# Domino_Single_Ethernet_PoE_No_Teardrop.net
KiCad netlist of a schematic drawn in EAGLE
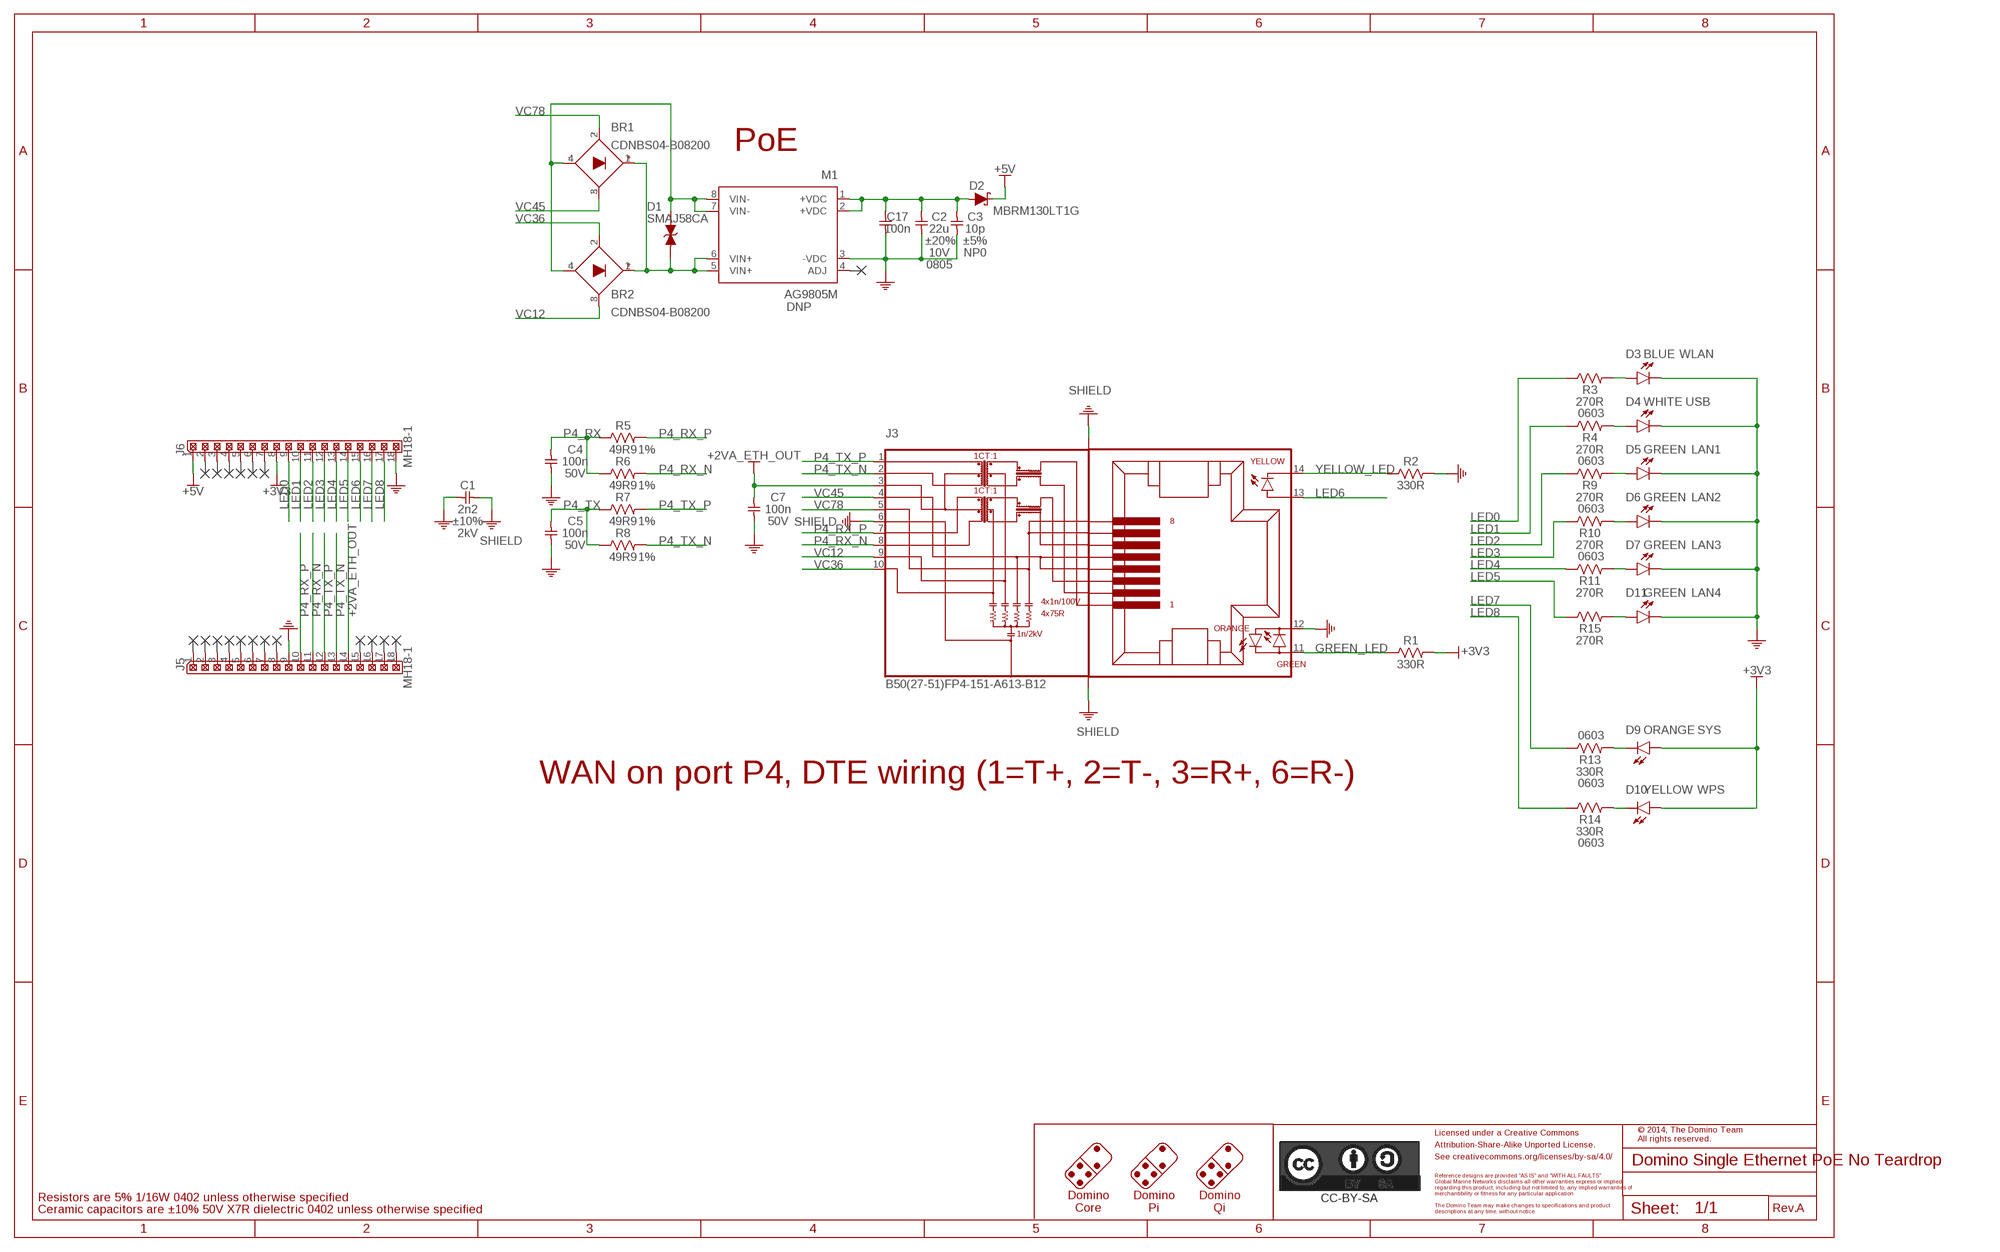
[diagram p0: schematic, sheet 1]

(export (version "E")
  (design (tool "Eeschema 10.0.6"))
  (components
    (comp (ref "BR1")
      (value "CDNBS04-B08200")
      (footprint "eagle-import:NBS04")
      (libsource (lib "eagle-import") (part "CDNBS04-B08200"))
    )
    (comp (ref "BR2")
      (value "CDNBS04-B08200")
      (footprint "eagle-import:NBS04")
      (libsource (lib "eagle-import") (part "CDNBS04-B08200"))
    )
    (comp (ref "C1")
      (value "2n2")
      (footprint "eagle-import:C1206")
      (fields
        (field (name "PARTNO") "C1210_2n2_X7R_10%_CER_2kV")
        (field (name "TOL") "±10%")
        (field (name "VOLT") "2kV")
      )
      (libsource (lib "eagle-import") (part "CAP_1206"))
    )
    (comp (ref "C2")
      (value "22u")
      (footprint "eagle-import:C0805")
      (fields
        (field (name "SIZE") "0805")
        (field (name "PARTNO") "C1206_22u_X7R_20%_CER_10V")
        (field (name "TOL") "±20%")
        (field (name "VOLT") "10V")
      )
      (libsource (lib "eagle-import") (part "CAP_0805"))
    )
    (comp (ref "C3")
      (value "10p")
      (footprint "eagle-import:C0402")
      (fields
        (field (name "PARTNO") "C0402_10p_NP0_5%_CER_50V")
        (field (name "TC") "NP0")
        (field (name "TOL") "±5%")
      )
      (libsource (lib "eagle-import") (part "CAP_0402"))
    )
    (comp (ref "C4")
      (value "100n")
      (footprint "eagle-import:C0402")
      (fields (field (name "PARTNO") "C0402_100n_X7R_10%_CER_50V") (field (name "VOLT") "50V"))
      (libsource (lib "eagle-import") (part "CAP_0402"))
    )
    (comp (ref "C5")
      (value "100n")
      (footprint "eagle-import:C0402")
      (fields (field (name "PARTNO") "C0402_100n_X7R_10%_CER_50V") (field (name "VOLT") "50V"))
      (libsource (lib "eagle-import") (part "CAP_0402"))
    )
    (comp (ref "C7")
      (value "100n")
      (footprint "eagle-import:C0402")
      (fields (field (name "PARTNO") "C0402_100n_X7R_10%_CER_50V") (field (name "VOLT") "50V"))
      (libsource (lib "eagle-import") (part "CAP_0402"))
    )
    (comp (ref "C17")
      (value "100n")
      (footprint "eagle-import:C0402")
      (fields (field (name "PARTNO") "C0402_100n_X7R_10%_CER_50V"))
      (libsource (lib "eagle-import") (part "CAP_0402"))
    )
    (comp (ref "CC-BY-SA1")
      (value "CC-BY-SA_LOGO")
      (footprint "eagle-import:CC-BY-SA_LOGO")
      (libsource (lib "eagle-import") (part "CC-BY-SA_LOGO"))
    )
    (comp (ref "D1")
      (value "SMAJ58CA")
      (footprint "eagle-import:SMA")
      (libsource (lib "eagle-import") (part "SMAJ58CA"))
    )
    (comp (ref "D2")
      (value "MBRM130LT1G")
      (footprint "eagle-import:DO-216AA")
      (libsource (lib "eagle-import") (part "MBRM130LT1G"))
    )
    (comp (ref "D3")
      (value "BLUE")
      (footprint "eagle-import:LED0603")
      (fields (field (name "PARTNO") "LED0603-BLUE"))
      (libsource (lib "eagle-import") (part "LED_0603"))
    )
    (comp (ref "D4")
      (value "WHITE")
      (footprint "eagle-import:LED0603")
      (fields (field (name "PARTNO") "LED0603-WHITE"))
      (libsource (lib "eagle-import") (part "LED_0603"))
    )
    (comp (ref "D5")
      (value "GREEN")
      (footprint "eagle-import:LED0603")
      (fields (field (name "PARTNO") "LED0603-GREEN"))
      (libsource (lib "eagle-import") (part "LED_0603"))
    )
    (comp (ref "D6")
      (value "GREEN")
      (footprint "eagle-import:LED0603")
      (fields (field (name "PARTNO") "LED0603-GREEN"))
      (libsource (lib "eagle-import") (part "LED_0603"))
    )
    (comp (ref "D7")
      (value "GREEN")
      (footprint "eagle-import:LED0603")
      (fields (field (name "PARTNO") "LED0603-GREEN"))
      (libsource (lib "eagle-import") (part "LED_0603"))
    )
    (comp (ref "D9")
      (value "ORANGE")
      (footprint "eagle-import:LED0603")
      (fields (field (name "PARTNO") "LED0603-ORANGE"))
      (libsource (lib "eagle-import") (part "LED_0603"))
    )
    (comp (ref "D10")
      (value "YELLOW")
      (footprint "eagle-import:LED0603")
      (fields (field (name "PARTNO") "LED0603-YELLOW"))
      (libsource (lib "eagle-import") (part "LED_0603"))
    )
    (comp (ref "D11")
      (value "GREEN")
      (footprint "eagle-import:LED0603")
      (fields (field (name "PARTNO") "LED0603-GREEN"))
      (libsource (lib "eagle-import") (part "LED_0603"))
    )
    (comp (ref "J3")
      (value "B50(27-51)FP4-151-A613-B12")
      (footprint "eagle-import:B50(27-51)FP4-151-A613-B12")
      (libsource (lib "eagle-import") (part "B50(27-51)FP4-151-A613-B12"))
    )
    (comp (ref "J5")
      (value "MH18-1")
      (footprint "eagle-import:MH18-1-0.1")
      (libsource (lib "eagle-import") (part "MH18-1"))
    )
    (comp (ref "J6")
      (value "MH18-1")
      (footprint "eagle-import:MH18-1-0.1")
      (libsource (lib "eagle-import") (part "MH18-1"))
    )
    (comp (ref "M1")
      (value "AG9805M")
      (footprint "eagle-import:AG9800M")
      (fields (field (name "PARTNO") "Ag9800M"))
      (libsource (lib "eagle-import") (part "AG98M05"))
    )
    (comp (ref "R1")
      (value "330R")
      (footprint "eagle-import:R0402")
      (fields (field (name "PARTNO") "R0402_330R_5%_62.5mW"))
      (libsource (lib "eagle-import") (part "RES_0402"))
    )
    (comp (ref "R2")
      (value "330R")
      (footprint "eagle-import:R0402")
      (fields (field (name "PARTNO") "R0402_330R_5%_62.5mW"))
      (libsource (lib "eagle-import") (part "RES_0402"))
    )
    (comp (ref "R3")
      (value "270R")
      (footprint "eagle-import:R0603")
      (fields (field (name "SIZE") "0603") (field (name "PARTNO") "R0603_270R_5%_125mW"))
      (libsource (lib "eagle-import") (part "RES_0603"))
    )
    (comp (ref "R4")
      (value "270R")
      (footprint "eagle-import:R0603")
      (fields (field (name "SIZE") "0603") (field (name "PARTNO") "R0603_270R_5%_125mW"))
      (libsource (lib "eagle-import") (part "RES_0603"))
    )
    (comp (ref "R5")
      (value "49R9")
      (footprint "eagle-import:R0402")
      (fields (field (name "PARTNO") "R0402_49R9_1%_62.5mW") (field (name "TOL") "1%"))
      (libsource (lib "eagle-import") (part "RES_0402"))
    )
    (comp (ref "R6")
      (value "49R9")
      (footprint "eagle-import:R0402")
      (fields (field (name "PARTNO") "R0402_49R9_1%_62.5mW") (field (name "TOL") "1%"))
      (libsource (lib "eagle-import") (part "RES_0402"))
    )
    (comp (ref "R7")
      (value "49R9")
      (footprint "eagle-import:R0402")
      (fields (field (name "PARTNO") "R0402_49R9_1%_62.5mW") (field (name "TOL") "1%"))
      (libsource (lib "eagle-import") (part "RES_0402"))
    )
    (comp (ref "R8")
      (value "49R9")
      (footprint "eagle-import:R0402")
      (fields (field (name "PARTNO") "R0402_49R9_1%_62.5mW") (field (name "TOL") "1%"))
      (libsource (lib "eagle-import") (part "RES_0402"))
    )
    (comp (ref "R9")
      (value "270R")
      (footprint "eagle-import:R0603")
      (fields (field (name "SIZE") "0603") (field (name "PARTNO") "R0603_270R_5%_125mW"))
      (libsource (lib "eagle-import") (part "RES_0603"))
    )
    (comp (ref "R10")
      (value "270R")
      (footprint "eagle-import:R0603")
      (fields (field (name "SIZE") "0603") (field (name "PARTNO") "R0603_270R_5%_125mW"))
      (libsource (lib "eagle-import") (part "RES_0603"))
    )
    (comp (ref "R11")
      (value "270R")
      (footprint "eagle-import:R0603")
      (fields (field (name "PARTNO") "R0603_270R_5%_125mW"))
      (libsource (lib "eagle-import") (part "RES_0603"))
    )
    (comp (ref "R13")
      (value "330R")
      (footprint "eagle-import:R0603")
      (fields (field (name "SIZE") "0603") (field (name "PARTNO") "R0603_330R_5%_125mW"))
      (libsource (lib "eagle-import") (part "RES_0603"))
    )
    (comp (ref "R14")
      (value "330R")
      (footprint "eagle-import:R0603")
      (fields (field (name "SIZE") "0603") (field (name "PARTNO") "R0603_330R_5%_125mW"))
      (libsource (lib "eagle-import") (part "RES_0603"))
    )
    (comp (ref "R15")
      (value "270R")
      (footprint "eagle-import:R0603")
      (fields (field (name "SIZE") "0603") (field (name "PARTNO") "R0603_270R_5%_125mW"))
      (libsource (lib "eagle-import") (part "RES_0603"))
    )
  )
  (nets
    (net (code "1") (name "+2VA_ETH_OUT") (class "Default")
      (node (ref "C7") (pin "2") (pinfunction "2_2") (pintype "passive"))
      (node (ref "J3") (pin "3") (pinfunction "3_3") (pintype "passive"))
      (node (ref "J5") (pin "14") (pinfunction "14_14") (pintype "passive"))
    )
    (net (code "2") (name "+3V3") (class "Default")
      (node (ref "D10") (pin "2") (pinfunction "A_2") (pintype "passive"))
      (node (ref "D9") (pin "2") (pinfunction "A_2") (pintype "passive"))
      (node (ref "J6") (pin "8") (pinfunction "8_8") (pintype "passive"))
      (node (ref "R1") (pin "2") (pinfunction "2_2") (pintype "passive"))
    )
    (net (code "3") (name "+5V") (class "Default")
      (node (ref "D2") (pin "1") (pinfunction "C_1") (pintype "passive"))
      (node (ref "J6") (pin "1") (pinfunction "1_1") (pintype "passive"))
    )
    (net (code "4") (name "/GREEN_LED") (class "Default")
      (node (ref "J3") (pin "11") (pinfunction "11_11") (pintype "passive"))
      (node (ref "R1") (pin "1") (pinfunction "1_1") (pintype "passive"))
    )
    (net (code "5") (name "/LED0") (class "Default")
      (node (ref "J6") (pin "9") (pinfunction "9_9") (pintype "passive"))
      (node (ref "R3") (pin "1") (pinfunction "1_1") (pintype "passive"))
    )
    (net (code "6") (name "/LED1") (class "Default")
      (node (ref "J6") (pin "10") (pinfunction "10_10") (pintype "passive"))
      (node (ref "R4") (pin "1") (pinfunction "1_1") (pintype "passive"))
    )
    (net (code "7") (name "/LED2") (class "Default")
      (node (ref "J6") (pin "11") (pinfunction "11_11") (pintype "passive"))
      (node (ref "R9") (pin "1") (pinfunction "1_1") (pintype "passive"))
    )
    (net (code "8") (name "/LED3") (class "Default")
      (node (ref "J6") (pin "12") (pinfunction "12_12") (pintype "passive"))
      (node (ref "R10") (pin "1") (pinfunction "1_1") (pintype "passive"))
    )
    (net (code "9") (name "/LED4") (class "Default")
      (node (ref "J6") (pin "13") (pinfunction "13_13") (pintype "passive"))
      (node (ref "R11") (pin "1") (pinfunction "1_1") (pintype "passive"))
    )
    (net (code "10") (name "/LED5") (class "Default")
      (node (ref "J6") (pin "14") (pinfunction "14_14") (pintype "passive"))
      (node (ref "R15") (pin "1") (pinfunction "1_1") (pintype "passive"))
    )
    (net (code "11") (name "/LED6") (class "Default")
      (node (ref "J3") (pin "13") (pinfunction "13_13") (pintype "passive"))
      (node (ref "J6") (pin "15") (pinfunction "15_15") (pintype "passive"))
    )
    (net (code "12") (name "/LED7") (class "Default")
      (node (ref "J6") (pin "16") (pinfunction "16_16") (pintype "passive"))
      (node (ref "R13") (pin "1") (pinfunction "1_1") (pintype "passive"))
    )
    (net (code "13") (name "/LED8") (class "Default")
      (node (ref "J6") (pin "17") (pinfunction "17_17") (pintype "passive"))
      (node (ref "R14") (pin "1") (pinfunction "1_1") (pintype "passive"))
    )
    (net (code "14") (name "/P4_RX") (class "Default")
      (node (ref "C4") (pin "2") (pinfunction "2_2") (pintype "passive"))
      (node (ref "R5") (pin "1") (pinfunction "1_1") (pintype "passive"))
      (node (ref "R6") (pin "1") (pinfunction "1_1") (pintype "passive"))
    )
    (net (code "15") (name "/P4_RX_N") (class "Default")
      (node (ref "J3") (pin "8") (pinfunction "8_8") (pintype "passive"))
      (node (ref "J5") (pin "11") (pinfunction "11_11") (pintype "passive"))
      (node (ref "R6") (pin "2") (pinfunction "2_2") (pintype "passive"))
    )
    (net (code "16") (name "/P4_RX_P") (class "Default")
      (node (ref "J3") (pin "7") (pinfunction "7_7") (pintype "passive"))
      (node (ref "J5") (pin "10") (pinfunction "10_10") (pintype "passive"))
      (node (ref "R5") (pin "2") (pinfunction "2_2") (pintype "passive"))
    )
    (net (code "17") (name "/P4_TX") (class "Default")
      (node (ref "C5") (pin "2") (pinfunction "2_2") (pintype "passive"))
      (node (ref "R7") (pin "1") (pinfunction "1_1") (pintype "passive"))
      (node (ref "R8") (pin "1") (pinfunction "1_1") (pintype "passive"))
    )
    (net (code "18") (name "/P4_TX_N") (class "Default")
      (node (ref "J3") (pin "2") (pinfunction "2_2") (pintype "passive"))
      (node (ref "J5") (pin "13") (pinfunction "13_13") (pintype "passive"))
      (node (ref "R8") (pin "2") (pinfunction "2_2") (pintype "passive"))
    )
    (net (code "19") (name "/P4_TX_P") (class "Default")
      (node (ref "J3") (pin "1") (pinfunction "1_1") (pintype "passive"))
      (node (ref "J5") (pin "12") (pinfunction "12_12") (pintype "passive"))
      (node (ref "R7") (pin "2") (pinfunction "2_2") (pintype "passive"))
    )
    (net (code "20") (name "/VC12") (class "Default")
      (node (ref "BR2") (pin "3") (pinfunction "AC2_3") (pintype "power_in"))
      (node (ref "J3") (pin "9") (pinfunction "9_9") (pintype "passive"))
    )
    (net (code "21") (name "/VC36") (class "Default")
      (node (ref "BR2") (pin "2") (pinfunction "AC1_2") (pintype "power_in"))
      (node (ref "J3") (pin "10") (pinfunction "10_10") (pintype "passive"))
    )
    (net (code "22") (name "/VC45") (class "Default")
      (node (ref "BR1") (pin "3") (pinfunction "AC2_3") (pintype "power_in"))
      (node (ref "J3") (pin "4") (pinfunction "4_4") (pintype "passive"))
    )
    (net (code "23") (name "/VC78") (class "Default")
      (node (ref "BR1") (pin "2") (pinfunction "AC1_2") (pintype "power_in"))
      (node (ref "J3") (pin "5") (pinfunction "5_5") (pintype "passive"))
    )
    (net (code "24") (name "/YELLOW_LED") (class "Default")
      (node (ref "J3") (pin "14") (pinfunction "14_14") (pintype "passive"))
      (node (ref "R2") (pin "1") (pinfunction "1_1") (pintype "passive"))
    )
    (net (code "25") (name "GND") (class "Default")
      (node (ref "C1") (pin "1") (pinfunction "1_1") (pintype "passive"))
      (node (ref "C17") (pin "2") (pinfunction "2_2") (pintype "passive"))
      (node (ref "C2") (pin "2") (pinfunction "2_2") (pintype "passive"))
      (node (ref "C3") (pin "2") (pinfunction "2_2") (pintype "passive"))
      (node (ref "C4") (pin "1") (pinfunction "1_1") (pintype "passive"))
      (node (ref "C5") (pin "1") (pinfunction "1_1") (pintype "passive"))
      (node (ref "C7") (pin "1") (pinfunction "1_1") (pintype "passive"))
      (node (ref "D11") (pin "1") (pinfunction "C_1") (pintype "passive"))
      (node (ref "D3") (pin "1") (pinfunction "C_1") (pintype "passive"))
      (node (ref "D4") (pin "1") (pinfunction "C_1") (pintype "passive"))
      (node (ref "D5") (pin "1") (pinfunction "C_1") (pintype "passive"))
      (node (ref "D6") (pin "1") (pinfunction "C_1") (pintype "passive"))
      (node (ref "D7") (pin "1") (pinfunction "C_1") (pintype "passive"))
      (node (ref "J3") (pin "12") (pinfunction "12_12") (pintype "passive"))
      (node (ref "J5") (pin "9") (pinfunction "9_9") (pintype "passive"))
      (node (ref "J6") (pin "18") (pinfunction "18_18") (pintype "passive"))
      (node (ref "M1") (pin "3") (pinfunction "-VDC_3") (pintype "power_in"))
      (node (ref "R2") (pin "2") (pinfunction "2_2") (pintype "passive"))
    )
    (net (code "26") (name "Net-(BR1-+)") (class "Default")
      (node (ref "BR1") (pin "1") (pinfunction "+_1") (pintype "power_in"))
      (node (ref "BR2") (pin "1") (pinfunction "+_1") (pintype "power_in"))
      (node (ref "D1") (pin "C") (pinfunction "2_C") (pintype "passive"))
      (node (ref "M1") (pin "5") (pinfunction "VIN+_5") (pintype "power_in"))
      (node (ref "M1") (pin "6") (pinfunction "VIN+_6") (pintype "power_in"))
    )
    (net (code "27") (name "Net-(BR1--)") (class "Default")
      (node (ref "BR1") (pin "4") (pinfunction "-_4") (pintype "power_in"))
      (node (ref "BR2") (pin "4") (pinfunction "-_4") (pintype "power_in"))
      (node (ref "D1") (pin "A") (pinfunction "1_A") (pintype "passive"))
      (node (ref "M1") (pin "7") (pinfunction "VIN-_7") (pintype "power_in"))
      (node (ref "M1") (pin "8") (pinfunction "VIN-_8") (pintype "power_in"))
    )
    (net (code "28") (name "Net-(D2-A)") (class "Default")
      (node (ref "C17") (pin "1") (pinfunction "1_1") (pintype "passive"))
      (node (ref "C2") (pin "1") (pinfunction "1_1") (pintype "passive"))
      (node (ref "C3") (pin "1") (pinfunction "1_1") (pintype "passive"))
      (node (ref "D2") (pin "2") (pinfunction "A_2") (pintype "passive"))
      (node (ref "M1") (pin "1") (pinfunction "+VDC_1") (pintype "power_in"))
      (node (ref "M1") (pin "2") (pinfunction "+VDC_2") (pintype "power_in"))
    )
    (net (code "29") (name "Net-(D3-A)") (class "Default")
      (node (ref "D3") (pin "2") (pinfunction "A_2") (pintype "passive"))
      (node (ref "R3") (pin "2") (pinfunction "2_2") (pintype "passive"))
    )
    (net (code "30") (name "Net-(D4-A)") (class "Default")
      (node (ref "D4") (pin "2") (pinfunction "A_2") (pintype "passive"))
      (node (ref "R4") (pin "2") (pinfunction "2_2") (pintype "passive"))
    )
    (net (code "31") (name "Net-(D5-A)") (class "Default")
      (node (ref "D5") (pin "2") (pinfunction "A_2") (pintype "passive"))
      (node (ref "R9") (pin "2") (pinfunction "2_2") (pintype "passive"))
    )
    (net (code "32") (name "Net-(D6-A)") (class "Default")
      (node (ref "D6") (pin "2") (pinfunction "A_2") (pintype "passive"))
      (node (ref "R10") (pin "2") (pinfunction "2_2") (pintype "passive"))
    )
    (net (code "33") (name "Net-(D7-A)") (class "Default")
      (node (ref "D7") (pin "2") (pinfunction "A_2") (pintype "passive"))
      (node (ref "R11") (pin "2") (pinfunction "2_2") (pintype "passive"))
    )
    (net (code "34") (name "Net-(D9-C)") (class "Default")
      (node (ref "D9") (pin "1") (pinfunction "C_1") (pintype "passive"))
      (node (ref "R13") (pin "2") (pinfunction "2_2") (pintype "passive"))
    )
    (net (code "35") (name "Net-(D10-C)") (class "Default")
      (node (ref "D10") (pin "1") (pinfunction "C_1") (pintype "passive"))
      (node (ref "R14") (pin "2") (pinfunction "2_2") (pintype "passive"))
    )
    (net (code "36") (name "Net-(D11-A)") (class "Default")
      (node (ref "D11") (pin "2") (pinfunction "A_2") (pintype "passive"))
      (node (ref "R15") (pin "2") (pinfunction "2_2") (pintype "passive"))
    )
    (net (code "37") (name "SHIELD") (class "Default")
      (node (ref "C1") (pin "2") (pinfunction "2_2") (pintype "passive"))
      (node (ref "J3") (pin "6") (pinfunction "6_6") (pintype "power_in"))
      (node (ref "J3") (pin "SH$1") (pinfunction "SHIELD_SH$1") (pintype "power_in"))
      (node (ref "J3") (pin "SH$2") (pinfunction "SHIELD_SH$2") (pintype "power_in"))
    )
    (net (code "38") (name "unconnected-(J5-Pad1)") (class "Default")
      (node (ref "J5") (pin "1") (pinfunction "1_1") (pintype "passive"))
    )
    (net (code "39") (name "unconnected-(J5-Pad2)") (class "Default")
      (node (ref "J5") (pin "2") (pinfunction "2_2") (pintype "passive"))
    )
    (net (code "40") (name "unconnected-(J5-Pad3)") (class "Default")
      (node (ref "J5") (pin "3") (pinfunction "3_3") (pintype "passive"))
    )
    (net (code "41") (name "unconnected-(J5-Pad4)") (class "Default")
      (node (ref "J5") (pin "4") (pinfunction "4_4") (pintype "passive"))
    )
    (net (code "42") (name "unconnected-(J5-Pad5)") (class "Default")
      (node (ref "J5") (pin "5") (pinfunction "5_5") (pintype "passive"))
    )
    (net (code "43") (name "unconnected-(J5-Pad6)") (class "Default")
      (node (ref "J5") (pin "6") (pinfunction "6_6") (pintype "passive"))
    )
    (net (code "44") (name "unconnected-(J5-Pad7)") (class "Default")
      (node (ref "J5") (pin "7") (pinfunction "7_7") (pintype "passive"))
    )
    (net (code "45") (name "unconnected-(J5-Pad8)") (class "Default")
      (node (ref "J5") (pin "8") (pinfunction "8_8") (pintype "passive"))
    )
    (net (code "46") (name "unconnected-(J5-Pad15)") (class "Default")
      (node (ref "J5") (pin "15") (pinfunction "15_15") (pintype "passive"))
    )
    (net (code "47") (name "unconnected-(J5-Pad16)") (class "Default")
      (node (ref "J5") (pin "16") (pinfunction "16_16") (pintype "passive"))
    )
    (net (code "48") (name "unconnected-(J5-Pad17)") (class "Default")
      (node (ref "J5") (pin "17") (pinfunction "17_17") (pintype "passive"))
    )
    (net (code "49") (name "unconnected-(J5-Pad18)") (class "Default")
      (node (ref "J5") (pin "18") (pinfunction "18_18") (pintype "passive"))
    )
    (net (code "50") (name "unconnected-(J6-Pad2)") (class "Default")
      (node (ref "J6") (pin "2") (pinfunction "2_2") (pintype "passive"))
    )
    (net (code "51") (name "unconnected-(J6-Pad3)") (class "Default")
      (node (ref "J6") (pin "3") (pinfunction "3_3") (pintype "passive"))
    )
    (net (code "52") (name "unconnected-(J6-Pad4)") (class "Default")
      (node (ref "J6") (pin "4") (pinfunction "4_4") (pintype "passive"))
    )
    (net (code "53") (name "unconnected-(J6-Pad5)") (class "Default")
      (node (ref "J6") (pin "5") (pinfunction "5_5") (pintype "passive"))
    )
    (net (code "54") (name "unconnected-(J6-Pad6)") (class "Default")
      (node (ref "J6") (pin "6") (pinfunction "6_6") (pintype "passive"))
    )
    (net (code "55") (name "unconnected-(J6-Pad7)") (class "Default")
      (node (ref "J6") (pin "7") (pinfunction "7_7") (pintype "passive"))
    )
    (net (code "56") (name "unconnected-(M1-ADJ-Pad4)") (class "Default")
      (node (ref "M1") (pin "4") (pinfunction "ADJ_4") (pintype "passive"))
    )
  )
)
